# Preamp.net
KiCad netlist of a schematic drawn in Altium Designer
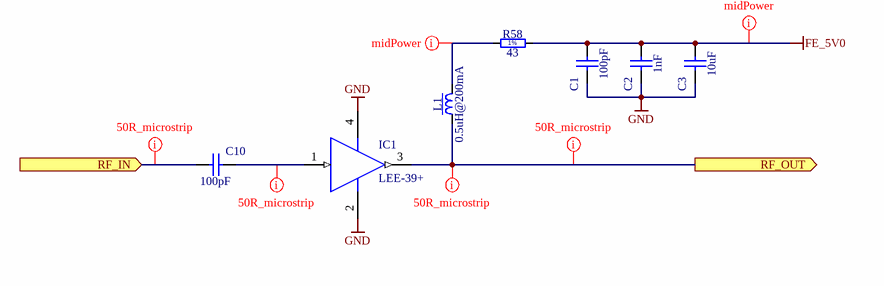
[diagram p0: Preamp.SchDoc]

(export (version "E")
  (design (tool "Eeschema 10.0.6"))
  (components
    (comp (ref "C1")
      (value "100pF")
      (footprint "CAPC1005X55N")
      (description "Non-polarised capacitor")
      (fields
        (field (name "PART NUMBER") "CC0402_100PF_50V_5%_C0G")
        (field (name "VOLTAGE") "50V")
        (field (name "AUTHOR") "CERN DEM JLC")
      )
      (libsource (lib "Capacitors") (part "Capacitor - non polarized"))
    )
    (comp (ref "C2")
      (value "1nF")
      (footprint "CAPC1005X55N")
      (description "Non-polarised capacitor")
      (fields
        (field (name "PART NUMBER") "CC0402_1NF_50V_10%_X7R")
        (field (name "VOLTAGE") "50V")
        (field (name "AUTHOR") "CERN DEM JLC")
      )
      (libsource (lib "Capacitors") (part "Capacitor - non polarized"))
    )
    (comp (ref "C3")
      (value "10uF")
      (footprint "CAPC3216X180N")
      (description "Non-polarised capacitor")
      (fields
        (field (name "PART NUMBER") "CC1206_10UF_25V_10%_X7R")
        (field (name "VOLTAGE") "25V")
        (field (name "AUTHOR") "CERN DEM JLC")
      )
      (libsource (lib "Capacitors") (part "Capacitor - non polarized"))
    )
    (comp (ref "C10")
      (value "100pF")
      (footprint "CAPC1005X55N")
      (description "Non-polarised capacitor")
      (fields
        (field (name "PART NUMBER") "CC0402_100PF_50V_5%_C0G")
        (field (name "VOLTAGE") "50V")
        (field (name "AUTHOR") "CERN DEM JLC")
      )
      (libsource (lib "Capacitors") (part "Capacitor - non polarized"))
    )
    (comp (ref "IC1")
      (value "LEE-39+")
      (footprint "MINI-CIRCUITS_FG873")
      (description "Monolithic Amplifier")
      (fields (field (name "MANUFACTURER") "MINI-CIRCUITS") (field (name "AUTHOR") "CERN DEM JLC"))
      (libsource (lib "ICs And Semiconductors") (part "Monolithic Amplifier Type 1"))
    )
    (comp (ref "L1")
      (value "0.5uH@200mA")
      (footprint "IND_MINI-CIRCUITS_GU1604")
      (description "50 Ohms, 50 to 8200 MHz RF Choke")
      (fields
        (field (name "PART NUMBER") "IND_MINI-CIRCUITS_TCCH-80+")
        (field (name "POWER") "200mA")
        (field (name "AUTHOR") "CERN DEM JLC")
      )
      (libsource (lib "Inductors & Transformers") (part "IND_MINI-CIRCUITS_TCCH-80+"))
    )
    (comp (ref "R58")
      (value "43")
      (footprint "RESC1608X55N")
      (description "Resistor - 1%")
      (fields
        (field (name "PART NUMBER") "R0603_43R_1%_0.1W_100PPM")
        (field (name "POWER") "0.1W")
        (field (name "AUTHOR") "CERN DEM JLC")
      )
      (libsource (lib "Resistors") (part "Resistor - 1%"))
    )
  )
  (nets
    (net (code "1") (name "/RF_IN") (class "Default")
      (node (ref "C10") (pin "1") (pinfunction "1_1") (pintype "passive"))
    )
    (net (code "2") (name "/RF_OUT") (class "Default")
      (node (ref "IC1") (pin "3") (pinfunction "RF_OUT_3") (pintype "output"))
      (node (ref "L1") (pin "1") (pinfunction "1_1") (pintype "passive"))
    )
    (net (code "3") (name "FE_5V0") (class "Default")
      (node (ref "C1") (pin "2") (pinfunction "2_2") (pintype "passive"))
      (node (ref "C2") (pin "2") (pinfunction "2_2") (pintype "passive"))
      (node (ref "C3") (pin "2") (pinfunction "2_2") (pintype "passive"))
      (node (ref "R58") (pin "2") (pinfunction "2_2") (pintype "passive"))
    )
    (net (code "4") (name "GND") (class "Default")
      (node (ref "C1") (pin "1") (pinfunction "1_1") (pintype "passive"))
      (node (ref "C2") (pin "1") (pinfunction "1_1") (pintype "passive"))
      (node (ref "C3") (pin "1") (pinfunction "1_1") (pintype "passive"))
      (node (ref "IC1") (pin "2") (pinfunction "GND_2") (pintype "power_in"))
      (node (ref "IC1") (pin "4") (pinfunction "GND_4") (pintype "power_in"))
    )
    (net (code "5") (name "Net-(IC1-RF_IN)") (class "Default")
      (node (ref "C10") (pin "2") (pinfunction "2_2") (pintype "passive"))
      (node (ref "IC1") (pin "1") (pinfunction "RF_IN_1") (pintype "input"))
    )
    (net (code "6") (name "Net-(L1-Pad3)") (class "Default")
      (node (ref "L1") (pin "3") (pinfunction "3_3") (pintype "passive"))
      (node (ref "R58") (pin "1") (pinfunction "1_1") (pintype "passive"))
    )
  )
)
